# EVmulator_T85_Proto.net
KiCad netlist of a schematic drawn in EAGLE
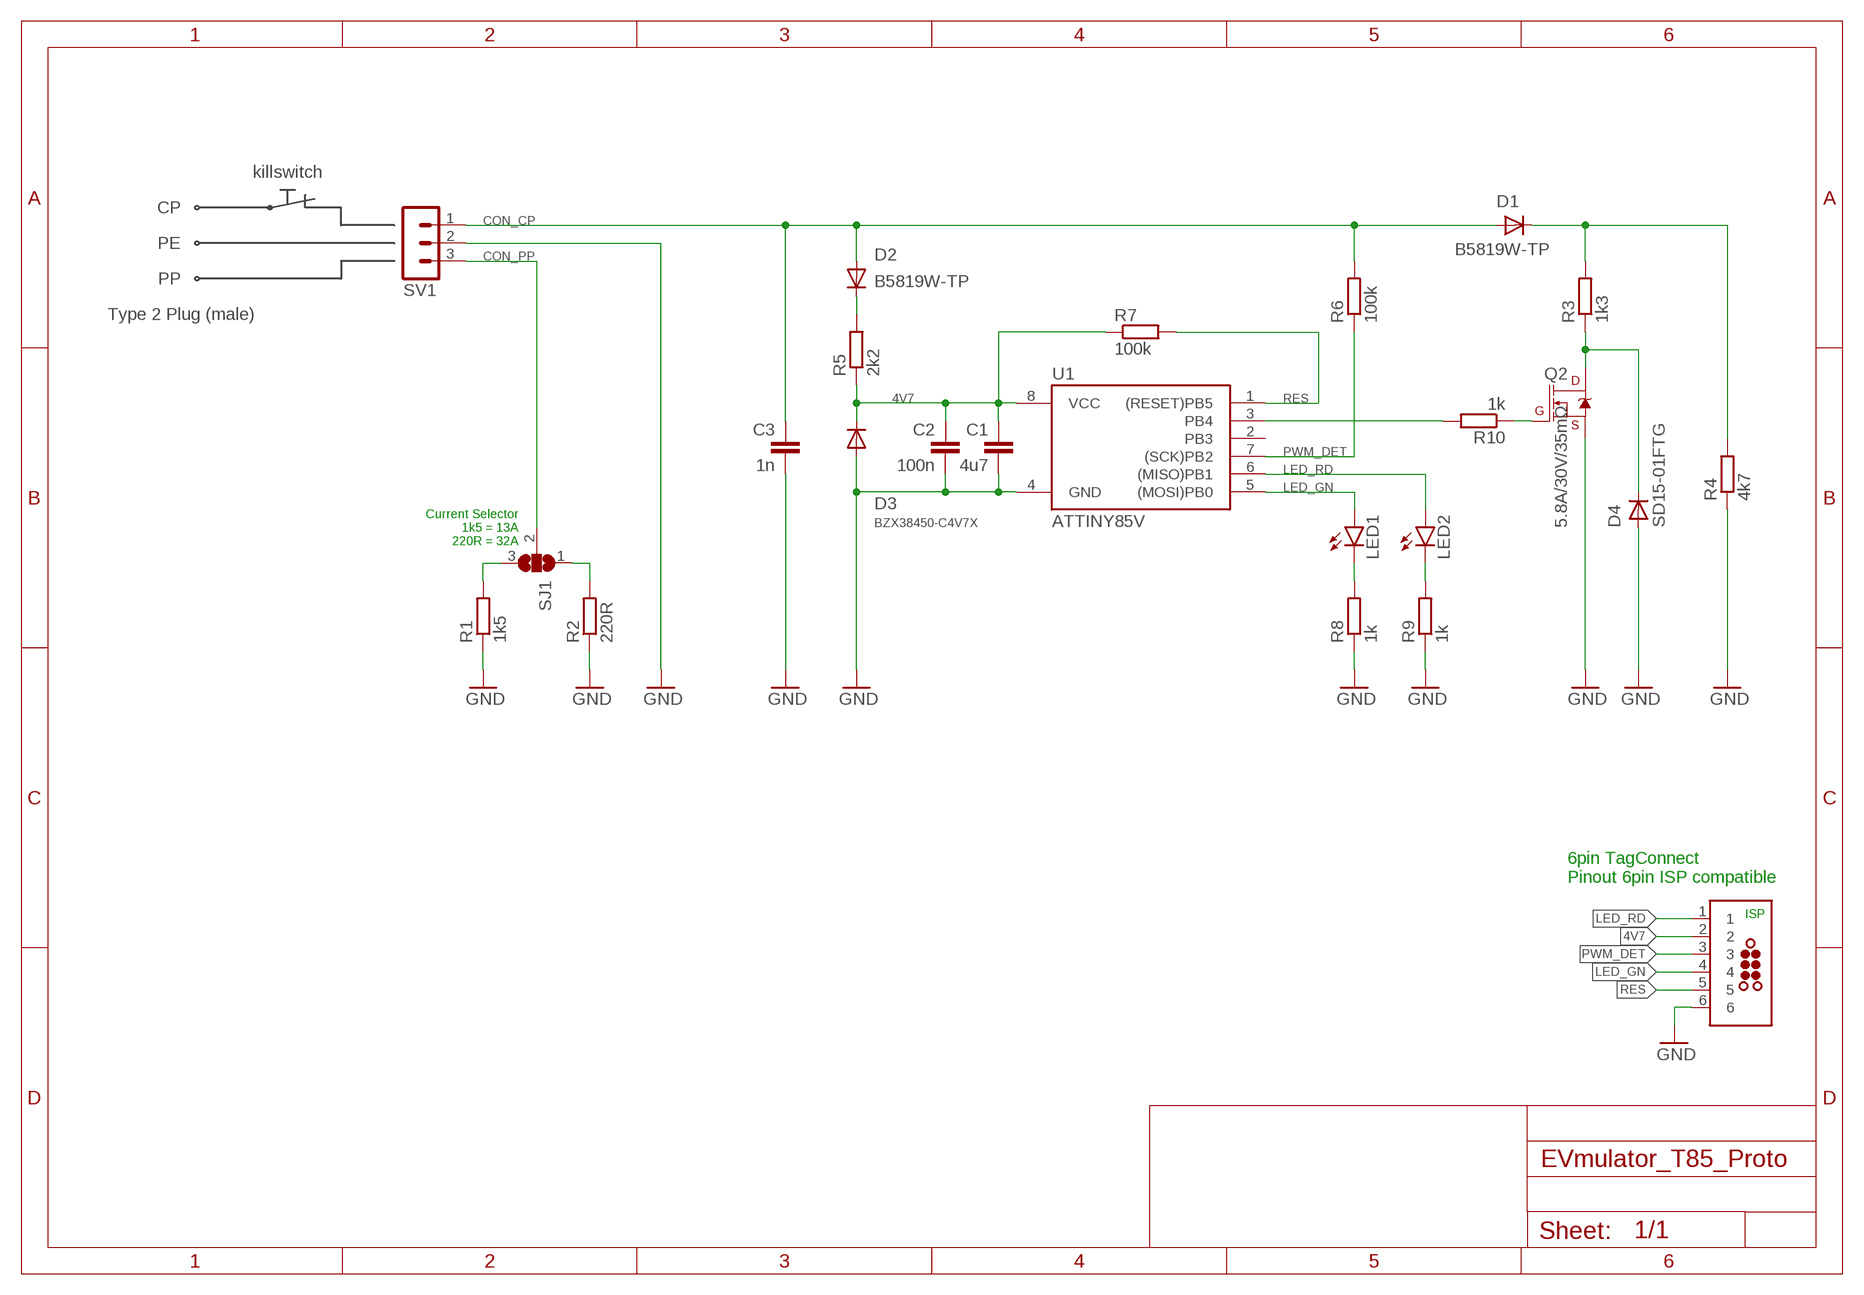
[diagram p0: schematic, sheet 1]

(export (version "E")
  (design (tool "Eeschema 10.0.6"))
  (components
    (comp (ref "C1")
      (value "4u7")
      (footprint "eagle-import:C0603")
      (libsource (lib "eagle-import") (part "C-EUC0603"))
    )
    (comp (ref "C2")
      (value "100n")
      (footprint "eagle-import:C0603")
      (libsource (lib "eagle-import") (part "C-EUC0603"))
    )
    (comp (ref "C3")
      (value "1n")
      (footprint "eagle-import:C0603")
      (libsource (lib "eagle-import") (part "C-EUC0603"))
    )
    (comp (ref "D1")
      (value "B5819W-TP")
      (footprint "eagle-import:SOD-123")
      (libsource (lib "eagle-import") (part "DIODESOD-123"))
    )
    (comp (ref "D2")
      (value "B5819W-TP")
      (footprint "eagle-import:SOD-123")
      (libsource (lib "eagle-import") (part "DIODESOD-123"))
    )
    (comp (ref "D3")
      (value "BZX38450-C4V7X")
      (footprint "eagle-import:SOD-323F")
      (libsource (lib "eagle-import") (part "DIODESOD-323F"))
    )
    (comp (ref "D4")
      (value "SD15-01FTG")
      (footprint "eagle-import:SOD-323F")
      (libsource (lib "eagle-import") (part "DIODESOD-323F"))
    )
    (comp (ref "J1")
      (value "TAG-CONNECT_TC2030-MCP-NL")
      (footprint "eagle-import:TAG-CONNECT_TC2030-MCP-NL")
      (libsource (lib "eagle-import") (part "TAG-CONNECT_TC2030-MCP-NL"))
    )
    (comp (ref "LED1")
      (value "LEDCHIP-LED0603")
      (footprint "eagle-import:CHIP-LED0603")
      (libsource (lib "eagle-import") (part "LEDCHIP-LED0603"))
    )
    (comp (ref "LED2")
      (value "LEDCHIP-LED0603")
      (footprint "eagle-import:CHIP-LED0603")
      (libsource (lib "eagle-import") (part "LEDCHIP-LED0603"))
    )
    (comp (ref "Q2")
      (value "5.8A/30V/35mΩ")
      (footprint "eagle-import:SOT23-3")
      (libsource (lib "eagle-import") (part "MOSFET-NCH-AO3404A"))
    )
    (comp (ref "R1")
      (value "1k5")
      (footprint "eagle-import:R0805")
      (libsource (lib "eagle-import") (part "R-EU_R0805"))
    )
    (comp (ref "R2")
      (value "220R")
      (footprint "eagle-import:R0805")
      (libsource (lib "eagle-import") (part "R-EU_R0805"))
    )
    (comp (ref "R3")
      (value "1k3")
      (footprint "eagle-import:R0603")
      (libsource (lib "eagle-import") (part "R-EU_R0603"))
    )
    (comp (ref "R4")
      (value "4k7")
      (footprint "eagle-import:R0603")
      (libsource (lib "eagle-import") (part "R-EU_R0603"))
    )
    (comp (ref "R5")
      (value "2k2")
      (footprint "eagle-import:R0603")
      (libsource (lib "eagle-import") (part "R-EU_R0603"))
    )
    (comp (ref "R6")
      (value "100k")
      (footprint "eagle-import:R0603")
      (libsource (lib "eagle-import") (part "R-EU_R0603"))
    )
    (comp (ref "R7")
      (value "100k")
      (footprint "eagle-import:R0603")
      (libsource (lib "eagle-import") (part "R-EU_R0603"))
    )
    (comp (ref "R8")
      (value "1k")
      (footprint "eagle-import:R0603")
      (libsource (lib "eagle-import") (part "R-EU_R0603"))
    )
    (comp (ref "R9")
      (value "1k")
      (footprint "eagle-import:R0603")
      (libsource (lib "eagle-import") (part "R-EU_R0603"))
    )
    (comp (ref "R10")
      (value "1k")
      (footprint "eagle-import:R0603")
      (libsource (lib "eagle-import") (part "R-EU_R0603"))
    )
    (comp (ref "SJ1")
      (value "SJ2W")
      (footprint "eagle-import:SJ_2")
      (libsource (lib "eagle-import") (part "SJ2W"))
    )
    (comp (ref "SV1")
      (value "MA03-1")
      (footprint "eagle-import:MA03-1")
      (libsource (lib "eagle-import") (part "MA03-1"))
    )
    (comp (ref "U1")
      (value "ATTINY85V")
      (footprint "eagle-import:SOIC8_200")
      (libsource (lib "eagle-import") (part "ATTINY25/45/85-20SU"))
    )
  )
  (nets
    (net (code "1") (name "/CON_CP") (class "Default")
      (node (ref "C3") (pin "1") (pinfunction "1_1") (pintype "passive"))
      (node (ref "D1") (pin "A") (pinfunction "A_A") (pintype "passive"))
      (node (ref "D2") (pin "A") (pinfunction "A_A") (pintype "passive"))
      (node (ref "R6") (pin "2") (pinfunction "2_2") (pintype "passive"))
      (node (ref "SV1") (pin "1") (pinfunction "1_1") (pintype "passive"))
    )
    (net (code "2") (name "/CON_PP") (class "Default")
      (node (ref "SJ1") (pin "2") (pinfunction "2_2") (pintype "passive"))
      (node (ref "SV1") (pin "3") (pinfunction "3_3") (pintype "passive"))
    )
    (net (code "3") (name "4V7") (class "Default")
      (node (ref "C1") (pin "1") (pinfunction "1_1") (pintype "passive"))
      (node (ref "C2") (pin "1") (pinfunction "1_1") (pintype "passive"))
      (node (ref "D3") (pin "C") (pinfunction "C_C") (pintype "passive"))
      (node (ref "J1") (pin "2") (pinfunction "2_2") (pintype "power_in"))
      (node (ref "R5") (pin "1") (pinfunction "1_1") (pintype "passive"))
      (node (ref "R7") (pin "1") (pinfunction "1_1") (pintype "passive"))
      (node (ref "U1") (pin "8") (pinfunction "VCC_8") (pintype "power_in"))
    )
    (net (code "4") (name "GND") (class "Default")
      (node (ref "C1") (pin "2") (pinfunction "2_2") (pintype "passive"))
      (node (ref "C2") (pin "2") (pinfunction "2_2") (pintype "passive"))
      (node (ref "C3") (pin "2") (pinfunction "2_2") (pintype "passive"))
      (node (ref "D3") (pin "A") (pinfunction "A_A") (pintype "passive"))
      (node (ref "D4") (pin "A") (pinfunction "A_A") (pintype "passive"))
      (node (ref "J1") (pin "6") (pinfunction "6_6") (pintype "bidirectional"))
      (node (ref "Q2") (pin "2") (pinfunction "S_2") (pintype "bidirectional"))
      (node (ref "R1") (pin "1") (pinfunction "1_1") (pintype "passive"))
      (node (ref "R2") (pin "1") (pinfunction "1_1") (pintype "passive"))
      (node (ref "R4") (pin "1") (pinfunction "1_1") (pintype "passive"))
      (node (ref "R8") (pin "1") (pinfunction "1_1") (pintype "passive"))
      (node (ref "R9") (pin "1") (pinfunction "1_1") (pintype "passive"))
      (node (ref "SV1") (pin "2") (pinfunction "2_2") (pintype "passive"))
      (node (ref "U1") (pin "4") (pinfunction "GND_4") (pintype "power_in"))
    )
    (net (code "5") (name "LED_GN") (class "Default")
      (node (ref "J1") (pin "4") (pinfunction "4_4") (pintype "bidirectional"))
      (node (ref "LED1") (pin "A") (pinfunction "A_A") (pintype "passive"))
      (node (ref "U1") (pin "5") (pinfunction "(MOSI)PB0_5") (pintype "bidirectional"))
    )
    (net (code "6") (name "LED_RD") (class "Default")
      (node (ref "J1") (pin "1") (pinfunction "1_1") (pintype "passive"))
      (node (ref "LED2") (pin "A") (pinfunction "A_A") (pintype "passive"))
      (node (ref "U1") (pin "6") (pinfunction "(MISO)PB1_6") (pintype "bidirectional"))
    )
    (net (code "7") (name "Net-(D1-PadC)") (class "Default")
      (node (ref "D1") (pin "C") (pinfunction "C_C") (pintype "passive"))
      (node (ref "R3") (pin "2") (pinfunction "2_2") (pintype "passive"))
      (node (ref "R4") (pin "2") (pinfunction "2_2") (pintype "passive"))
    )
    (net (code "8") (name "Net-(D2-PadC)") (class "Default")
      (node (ref "D2") (pin "C") (pinfunction "C_C") (pintype "passive"))
      (node (ref "R5") (pin "2") (pinfunction "2_2") (pintype "passive"))
    )
    (net (code "9") (name "Net-(LED1-PadC)") (class "Default")
      (node (ref "LED1") (pin "C") (pinfunction "C_C") (pintype "passive"))
      (node (ref "R8") (pin "2") (pinfunction "2_2") (pintype "passive"))
    )
    (net (code "10") (name "Net-(LED2-PadC)") (class "Default")
      (node (ref "LED2") (pin "C") (pinfunction "C_C") (pintype "passive"))
      (node (ref "R9") (pin "2") (pinfunction "2_2") (pintype "passive"))
    )
    (net (code "11") (name "Net-(Q2-D)") (class "Default")
      (node (ref "D4") (pin "C") (pinfunction "C_C") (pintype "passive"))
      (node (ref "Q2") (pin "3") (pinfunction "D_3") (pintype "bidirectional"))
      (node (ref "R3") (pin "1") (pinfunction "1_1") (pintype "passive"))
    )
    (net (code "12") (name "Net-(Q2-G)") (class "Default")
      (node (ref "Q2") (pin "1") (pinfunction "G_1") (pintype "bidirectional"))
      (node (ref "R10") (pin "1") (pinfunction "1_1") (pintype "passive"))
    )
    (net (code "13") (name "Net-(R1-Pad2)") (class "Default")
      (node (ref "R1") (pin "2") (pinfunction "2_2") (pintype "passive"))
      (node (ref "SJ1") (pin "3") (pinfunction "3_3") (pintype "passive"))
    )
    (net (code "14") (name "Net-(R2-Pad2)") (class "Default")
      (node (ref "R2") (pin "2") (pinfunction "2_2") (pintype "passive"))
      (node (ref "SJ1") (pin "1") (pinfunction "1_1") (pintype "passive"))
    )
    (net (code "15") (name "Net-(U1-PB4)") (class "Default")
      (node (ref "R10") (pin "2") (pinfunction "2_2") (pintype "passive"))
      (node (ref "U1") (pin "3") (pinfunction "PB4_3") (pintype "bidirectional"))
    )
    (net (code "16") (name "PWM_DET") (class "Default")
      (node (ref "J1") (pin "3") (pinfunction "3_3") (pintype "power_in"))
      (node (ref "R6") (pin "1") (pinfunction "1_1") (pintype "passive"))
      (node (ref "U1") (pin "7") (pinfunction "(SCK)PB2_7") (pintype "bidirectional"))
    )
    (net (code "17") (name "RES") (class "Default")
      (node (ref "J1") (pin "5") (pinfunction "5_5") (pintype "output"))
      (node (ref "R7") (pin "2") (pinfunction "2_2") (pintype "passive"))
      (node (ref "U1") (pin "1") (pinfunction "(RESET)PB5_1") (pintype "bidirectional"))
    )
    (net (code "18") (name "unconnected-(U1-PB3-Pad2)") (class "Default")
      (node (ref "U1") (pin "2") (pinfunction "PB3_2") (pintype "bidirectional"))
    )
  )
)
